# Bases_Aire_Sensors_v4.net
KiCad netlist of a schematic drawn in EAGLE
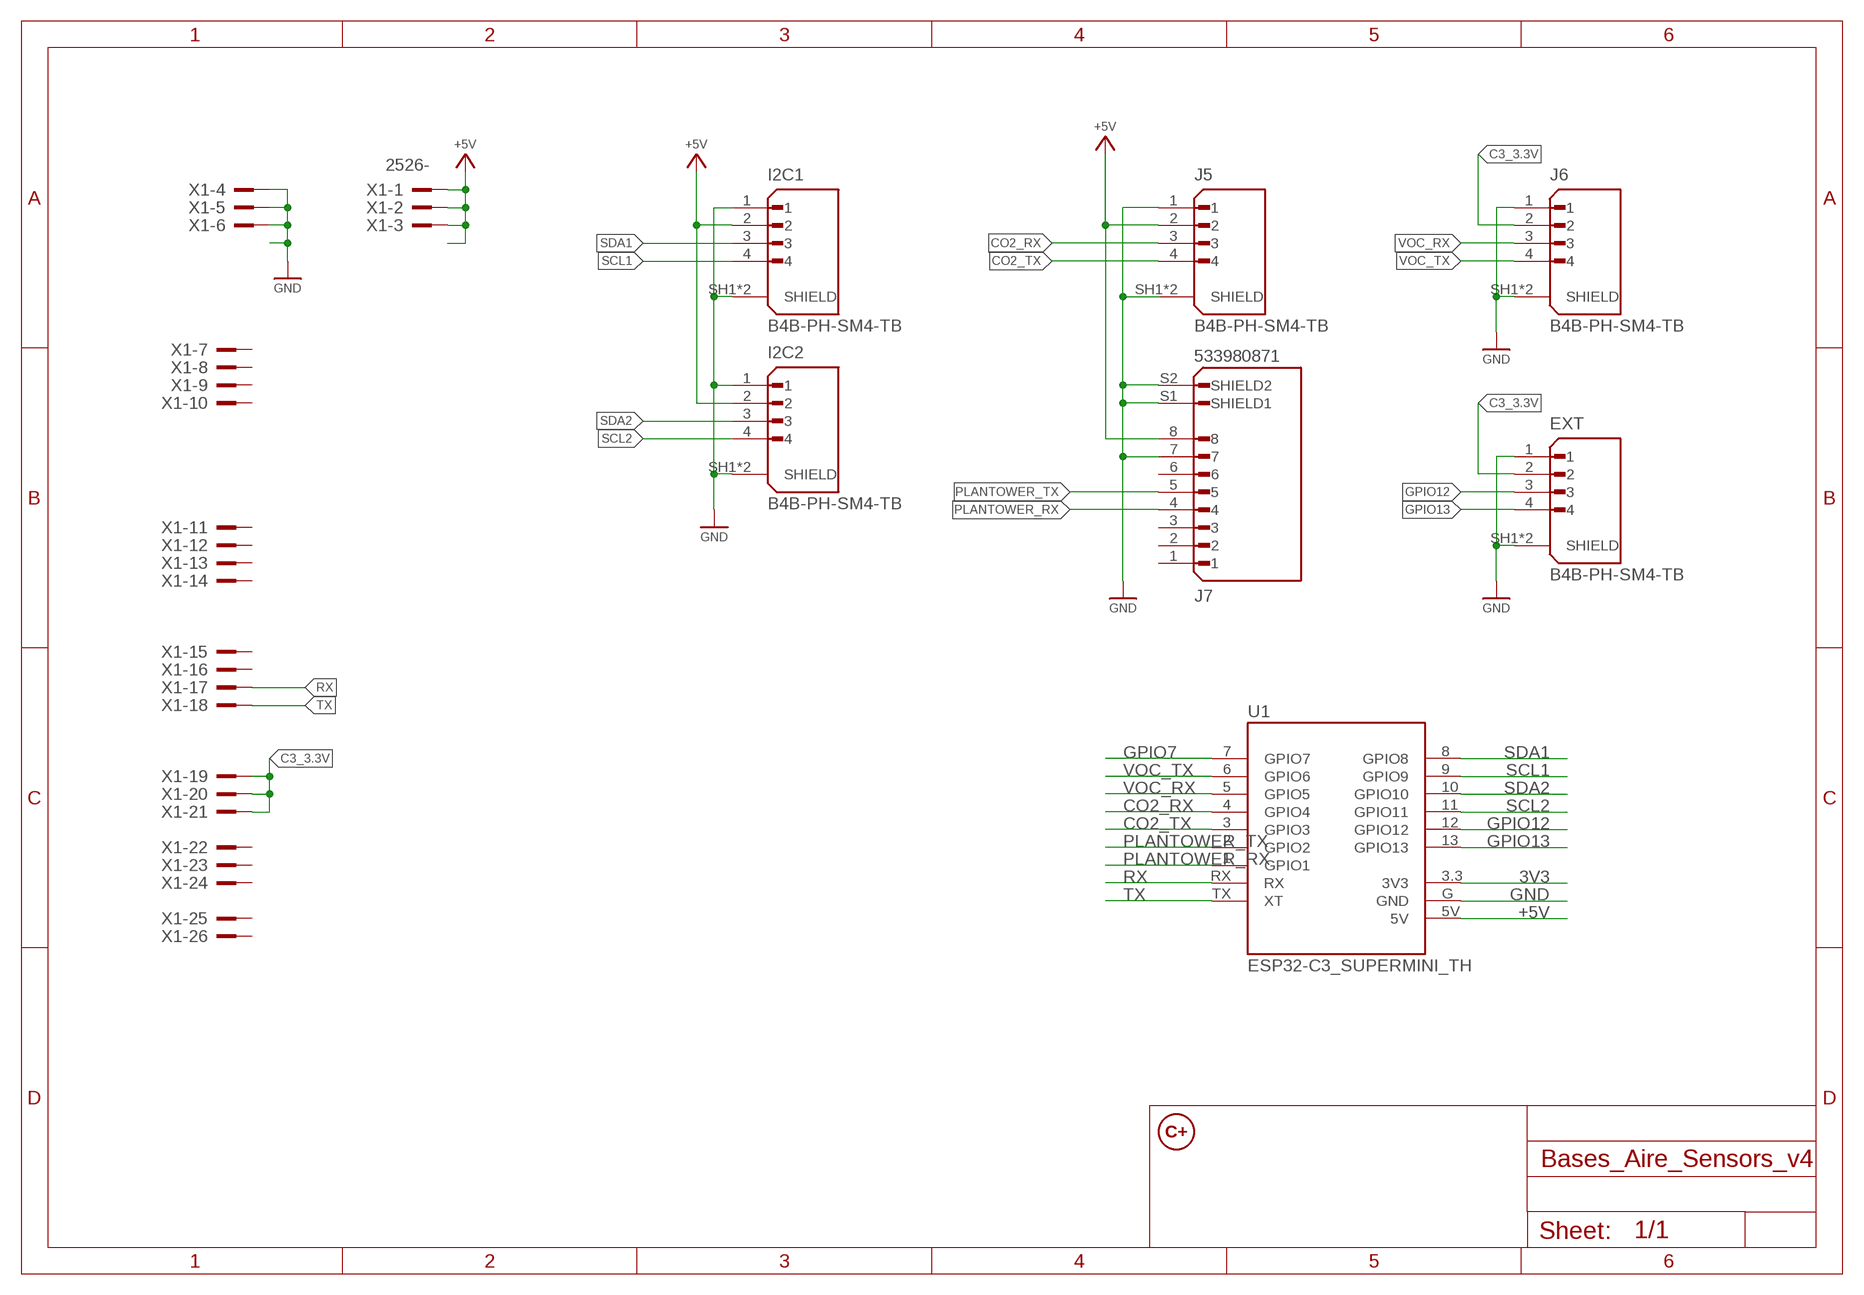
[diagram p0: schematic, sheet 1]

(export (version "E")
  (design (tool "Eeschema 10.0.6"))
  (components
    (comp (ref "EXT")
      (value "B4B-PH-SM4-TB")
      (footprint "eagle-import:JST_B4B-PH-SM4-TB")
      (fields (field (name "MF") "JST Sales"))
      (libsource (lib "eagle-import") (part "B4B-PH-SM4-TB"))
    )
    (comp (ref "I2C1")
      (value "B4B-PH-SM4-TB")
      (footprint "eagle-import:JST_B4B-PH-SM4-TB")
      (fields (field (name "MF") "JST Sales"))
      (libsource (lib "eagle-import") (part "B4B-PH-SM4-TB"))
    )
    (comp (ref "I2C2")
      (value "B4B-PH-SM4-TB")
      (footprint "eagle-import:JST_B4B-PH-SM4-TB")
      (fields (field (name "MF") "JST Sales"))
      (libsource (lib "eagle-import") (part "B4B-PH-SM4-TB"))
    )
    (comp (ref "J5")
      (value "B4B-PH-SM4-TB")
      (footprint "eagle-import:JST_B4B-PH-SM4-TB")
      (fields (field (name "MF") "JST Sales"))
      (libsource (lib "eagle-import") (part "B4B-PH-SM4-TB"))
    )
    (comp (ref "J6")
      (value "B4B-PH-SM4-TB")
      (footprint "eagle-import:JST_B4B-PH-SM4-TB")
      (fields (field (name "MF") "JST Sales"))
      (libsource (lib "eagle-import") (part "B4B-PH-SM4-TB"))
    )
    (comp (ref "J7")
      (value "533980871")
      (footprint "eagle-import:MOLEX_533980871")
      (fields (field (name "MF") "Molex") (field (name "MP") "53398-0871"))
      (libsource (lib "eagle-import") (part "533980871"))
    )
    (comp (ref "U$1")
      (value "LOGO_CMAS10MM")
      (footprint "eagle-import:LOGO_10MM")
      (libsource (lib "eagle-import") (part "LOGO_CMAS10MM"))
    )
    (comp (ref "U1")
      (value "ESP32-C3_SUPERMINI_TH")
      (footprint "eagle-import:MODULE_ESP32-C3_SUPERMINI_TH")
      (fields (field (name "MF") "Espressif Systems") (field (name "MP") "ESP32-S3 SuperMini_TH"))
      (libsource (lib "eagle-import") (part "ESP32-C3_SUPERMINI_TH"))
    )
    (comp (ref "X1")
      (value "2526-")
      (footprint "eagle-import:PAK100_2500-26")
      (libsource (lib "eagle-import") (part "2526-"))
    )
  )
  (nets
    (net (code "1") (name "+5V") (class "Default")
      (node (ref "I2C1") (pin "2") (pinfunction "2_2") (pintype "passive"))
      (node (ref "I2C2") (pin "2") (pinfunction "2_2") (pintype "passive"))
      (node (ref "J5") (pin "2") (pinfunction "2_2") (pintype "passive"))
      (node (ref "J7") (pin "8") (pinfunction "8_8") (pintype "passive"))
      (node (ref "U1") (pin "5V") (pinfunction "5V_5V") (pintype "power_in"))
      (node (ref "X1") (pin "1") (pinfunction "KL_1") (pintype "passive"))
      (node (ref "X1") (pin "2") (pinfunction "KL_2") (pintype "passive"))
      (node (ref "X1") (pin "3") (pinfunction "KL_3") (pintype "passive"))
    )
    (net (code "2") (name "/3V3") (class "Default")
      (node (ref "U1") (pin "3.3") (pinfunction "3V3_3.3") (pintype "power_in"))
    )
    (net (code "3") (name "/GPIO7") (class "Default")
      (node (ref "U1") (pin "7") (pinfunction "GPIO7_7") (pintype "bidirectional"))
    )
    (net (code "4") (name "C3_3.3V") (class "Default")
      (node (ref "EXT") (pin "2") (pinfunction "2_2") (pintype "passive"))
      (node (ref "J6") (pin "2") (pinfunction "2_2") (pintype "passive"))
      (node (ref "X1") (pin "19") (pinfunction "KL_19") (pintype "passive"))
      (node (ref "X1") (pin "20") (pinfunction "KL_20") (pintype "passive"))
      (node (ref "X1") (pin "21") (pinfunction "KL_21") (pintype "passive"))
    )
    (net (code "5") (name "CO2_RX") (class "Default")
      (node (ref "J5") (pin "3") (pinfunction "3_3") (pintype "passive"))
      (node (ref "U1") (pin "4") (pinfunction "GPIO4_4") (pintype "bidirectional"))
    )
    (net (code "6") (name "CO2_TX") (class "Default")
      (node (ref "J5") (pin "4") (pinfunction "4_4") (pintype "passive"))
      (node (ref "U1") (pin "3") (pinfunction "GPIO3_3") (pintype "bidirectional"))
    )
    (net (code "7") (name "GND") (class "Default")
      (node (ref "EXT") (pin "1") (pinfunction "1_1") (pintype "passive"))
      (node (ref "EXT") (pin "SH1") (pinfunction "SHIELD_SH1") (pintype "passive"))
      (node (ref "EXT") (pin "SH2") (pinfunction "SHIELD_SH2") (pintype "passive"))
      (node (ref "I2C1") (pin "1") (pinfunction "1_1") (pintype "passive"))
      (node (ref "I2C1") (pin "SH1") (pinfunction "SHIELD_SH1") (pintype "passive"))
      (node (ref "I2C1") (pin "SH2") (pinfunction "SHIELD_SH2") (pintype "passive"))
      (node (ref "I2C2") (pin "1") (pinfunction "1_1") (pintype "passive"))
      (node (ref "I2C2") (pin "SH1") (pinfunction "SHIELD_SH1") (pintype "passive"))
      (node (ref "I2C2") (pin "SH2") (pinfunction "SHIELD_SH2") (pintype "passive"))
      (node (ref "J5") (pin "1") (pinfunction "1_1") (pintype "passive"))
      (node (ref "J5") (pin "SH1") (pinfunction "SHIELD_SH1") (pintype "passive"))
      (node (ref "J5") (pin "SH2") (pinfunction "SHIELD_SH2") (pintype "passive"))
      (node (ref "J6") (pin "1") (pinfunction "1_1") (pintype "passive"))
      (node (ref "J6") (pin "SH1") (pinfunction "SHIELD_SH1") (pintype "passive"))
      (node (ref "J6") (pin "SH2") (pinfunction "SHIELD_SH2") (pintype "passive"))
      (node (ref "J7") (pin "7") (pinfunction "7_7") (pintype "passive"))
      (node (ref "J7") (pin "S1") (pinfunction "SHIELD1_S1") (pintype "passive"))
      (node (ref "J7") (pin "S2") (pinfunction "SHIELD2_S2") (pintype "passive"))
      (node (ref "U1") (pin "G") (pinfunction "GND_G") (pintype "power_in"))
      (node (ref "X1") (pin "4") (pinfunction "KL_4") (pintype "passive"))
      (node (ref "X1") (pin "5") (pinfunction "KL_5") (pintype "passive"))
      (node (ref "X1") (pin "6") (pinfunction "KL_6") (pintype "passive"))
    )
    (net (code "8") (name "GPIO12") (class "Default")
      (node (ref "EXT") (pin "3") (pinfunction "3_3") (pintype "passive"))
      (node (ref "U1") (pin "12") (pinfunction "GPIO12_12") (pintype "bidirectional"))
    )
    (net (code "9") (name "GPIO13") (class "Default")
      (node (ref "EXT") (pin "4") (pinfunction "4_4") (pintype "passive"))
      (node (ref "U1") (pin "13") (pinfunction "GPIO13_13") (pintype "bidirectional"))
    )
    (net (code "10") (name "PLANTOWER_RX") (class "Default")
      (node (ref "J7") (pin "4") (pinfunction "4_4") (pintype "passive"))
      (node (ref "U1") (pin "1") (pinfunction "GPIO1_1") (pintype "bidirectional"))
    )
    (net (code "11") (name "PLANTOWER_TX") (class "Default")
      (node (ref "J7") (pin "5") (pinfunction "5_5") (pintype "passive"))
      (node (ref "U1") (pin "2") (pinfunction "GPIO2_2") (pintype "bidirectional"))
    )
    (net (code "12") (name "RX") (class "Default")
      (node (ref "U1") (pin "RX") (pinfunction "RX_RX") (pintype "bidirectional"))
      (node (ref "X1") (pin "17") (pinfunction "KL_17") (pintype "passive"))
    )
    (net (code "13") (name "SCL1") (class "Default")
      (node (ref "I2C1") (pin "4") (pinfunction "4_4") (pintype "passive"))
      (node (ref "U1") (pin "9") (pinfunction "GPIO9_9") (pintype "bidirectional"))
    )
    (net (code "14") (name "SCL2") (class "Default")
      (node (ref "I2C2") (pin "4") (pinfunction "4_4") (pintype "passive"))
      (node (ref "U1") (pin "11") (pinfunction "GPIO11_11") (pintype "bidirectional"))
    )
    (net (code "15") (name "SDA1") (class "Default")
      (node (ref "I2C1") (pin "3") (pinfunction "3_3") (pintype "passive"))
      (node (ref "U1") (pin "8") (pinfunction "GPIO8_8") (pintype "bidirectional"))
    )
    (net (code "16") (name "SDA2") (class "Default")
      (node (ref "I2C2") (pin "3") (pinfunction "3_3") (pintype "passive"))
      (node (ref "U1") (pin "10") (pinfunction "GPIO10_10") (pintype "bidirectional"))
    )
    (net (code "17") (name "TX") (class "Default")
      (node (ref "U1") (pin "TX") (pinfunction "XT_TX") (pintype "bidirectional"))
      (node (ref "X1") (pin "18") (pinfunction "KL_18") (pintype "passive"))
    )
    (net (code "18") (name "VOC_RX") (class "Default")
      (node (ref "J6") (pin "3") (pinfunction "3_3") (pintype "passive"))
      (node (ref "U1") (pin "5") (pinfunction "GPIO5_5") (pintype "bidirectional"))
    )
    (net (code "19") (name "VOC_TX") (class "Default")
      (node (ref "J6") (pin "4") (pinfunction "4_4") (pintype "passive"))
      (node (ref "U1") (pin "6") (pinfunction "GPIO6_6") (pintype "bidirectional"))
    )
    (net (code "20") (name "unconnected-(J7-Pad1)") (class "Default")
      (node (ref "J7") (pin "1") (pinfunction "1_1") (pintype "passive"))
    )
    (net (code "21") (name "unconnected-(J7-Pad2)") (class "Default")
      (node (ref "J7") (pin "2") (pinfunction "2_2") (pintype "passive"))
    )
    (net (code "22") (name "unconnected-(J7-Pad3)") (class "Default")
      (node (ref "J7") (pin "3") (pinfunction "3_3") (pintype "passive"))
    )
    (net (code "23") (name "unconnected-(J7-Pad6)") (class "Default")
      (node (ref "J7") (pin "6") (pinfunction "6_6") (pintype "passive"))
    )
    (net (code "24") (name "unconnected-(X1B-KL-Pad10)") (class "Default")
      (node (ref "X1") (pin "10") (pinfunction "KL_10") (pintype "passive"))
    )
    (net (code "25") (name "unconnected-(X1C-KL-Pad11)") (class "Default")
      (node (ref "X1") (pin "11") (pinfunction "KL_11") (pintype "passive"))
    )
    (net (code "26") (name "unconnected-(X1D-KL-Pad12)") (class "Default")
      (node (ref "X1") (pin "12") (pinfunction "KL_12") (pintype "passive"))
    )
    (net (code "27") (name "unconnected-(X1E-KL-Pad13)") (class "Default")
      (node (ref "X1") (pin "13") (pinfunction "KL_13") (pintype "passive"))
    )
    (net (code "28") (name "unconnected-(X1F-KL-Pad14)") (class "Default")
      (node (ref "X1") (pin "14") (pinfunction "KL_14") (pintype "passive"))
    )
    (net (code "29") (name "unconnected-(X1G-KL-Pad15)") (class "Default")
      (node (ref "X1") (pin "15") (pinfunction "KL_15") (pintype "passive"))
    )
    (net (code "30") (name "unconnected-(X1H-KL-Pad16)") (class "Default")
      (node (ref "X1") (pin "16") (pinfunction "KL_16") (pintype "passive"))
    )
    (net (code "31") (name "unconnected-(X1O-KL-Pad22)") (class "Default")
      (node (ref "X1") (pin "22") (pinfunction "KL_22") (pintype "passive"))
    )
    (net (code "32") (name "unconnected-(X1P-KL-Pad23)") (class "Default")
      (node (ref "X1") (pin "23") (pinfunction "KL_23") (pintype "passive"))
    )
    (net (code "33") (name "unconnected-(X1Q-KL-Pad24)") (class "Default")
      (node (ref "X1") (pin "24") (pinfunction "KL_24") (pintype "passive"))
    )
    (net (code "34") (name "unconnected-(X1R-KL-Pad25)") (class "Default")
      (node (ref "X1") (pin "25") (pinfunction "KL_25") (pintype "passive"))
    )
    (net (code "35") (name "unconnected-(X1S-KL-Pad26)") (class "Default")
      (node (ref "X1") (pin "26") (pinfunction "KL_26") (pintype "passive"))
    )
    (net (code "36") (name "unconnected-(X1X-KL-Pad7)") (class "Default")
      (node (ref "X1") (pin "7") (pinfunction "KL_7") (pintype "passive"))
    )
    (net (code "37") (name "unconnected-(X1Y-KL-Pad8)") (class "Default")
      (node (ref "X1") (pin "8") (pinfunction "KL_8") (pintype "passive"))
    )
    (net (code "38") (name "unconnected-(X1Z-KL-Pad9)") (class "Default")
      (node (ref "X1") (pin "9") (pinfunction "KL_9") (pintype "passive"))
    )
  )
)
